# QFN-16_0_5mm.net
KiCad netlist of a schematic drawn in EAGLE
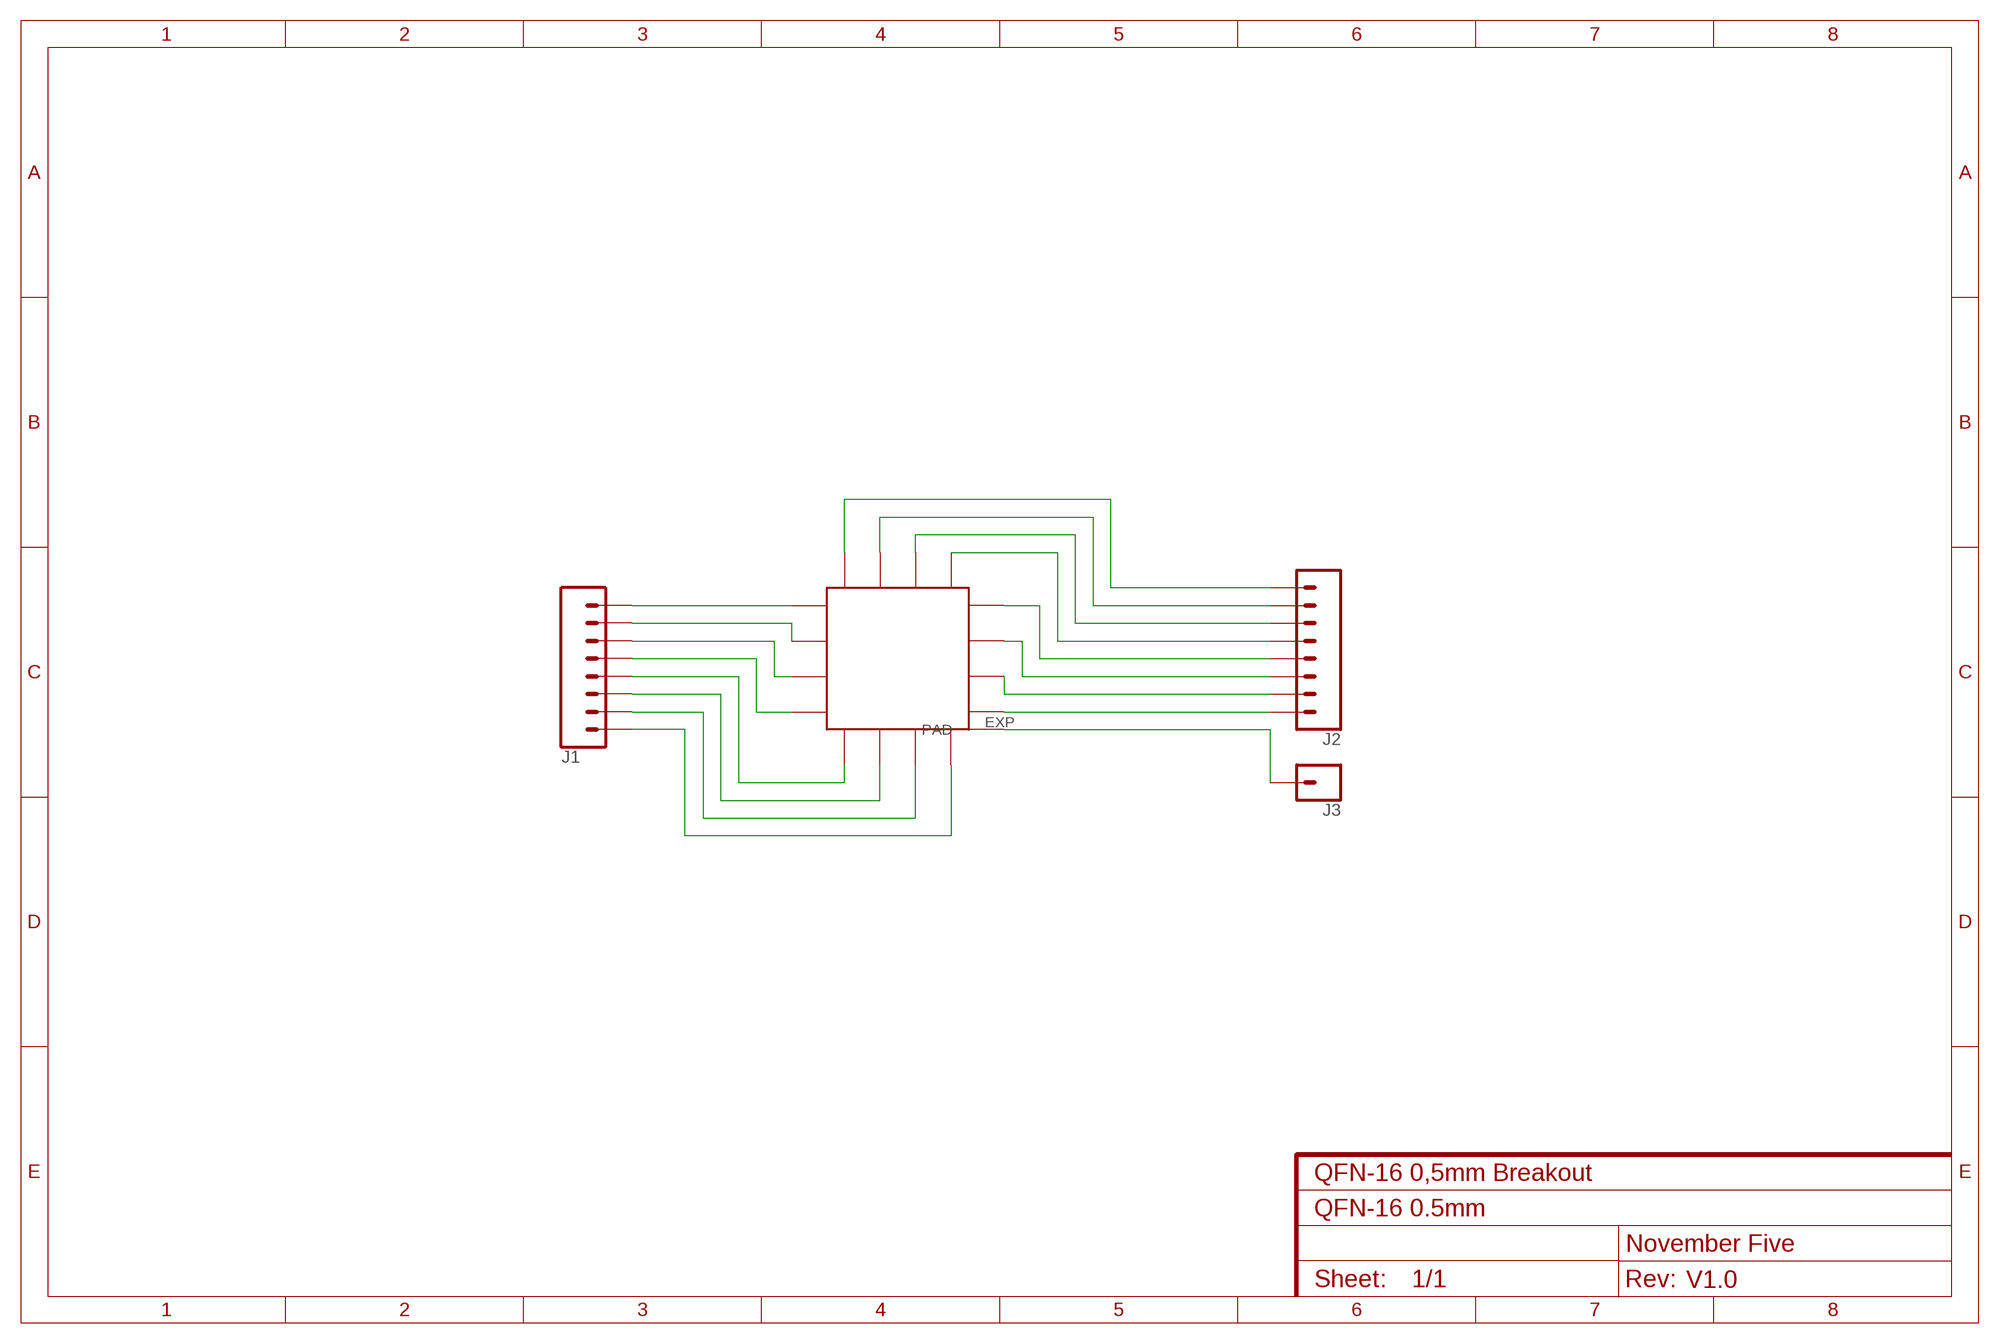
[diagram p0: schematic, sheet 1]

(export (version "E")
  (design (tool "Eeschema 10.0.6"))
  (components
    (comp (ref "J1")
      (value "CONN_08\"")
      (footprint "eagle-import:1X08")
      (libsource (lib "eagle-import") (part "CONN_08{dblquote}"))
    )
    (comp (ref "J2")
      (value "CONN_08\"")
      (footprint "eagle-import:1X08")
      (libsource (lib "eagle-import") (part "CONN_08{dblquote}"))
    )
    (comp (ref "J3")
      (value "CONN_01")
      (footprint "eagle-import:1X01")
      (libsource (lib "eagle-import") (part "CONN_01"))
    )
    (comp (ref "U$1")
      (value "QFN-16_0,5MM")
      (footprint "eagle-import:QFN16_0,5MM")
      (libsource (lib "eagle-import") (part "QFN-16_0,5MM"))
    )
  )
  (nets
    (net (code "1") (name "Net-(U$1-PAD)") (class "Default")
      (node (ref "J3") (pin "1") (pinfunction "1_1") (pintype "passive"))
      (node (ref "U$1") (pin "EXP") (pinfunction "PAD_EXP") (pintype "bidirectional"))
    )
    (net (code "2") (name "Net-(U$1-PIN1)") (class "Default")
      (node (ref "J1") (pin "1") (pinfunction "1_1") (pintype "passive"))
      (node (ref "U$1") (pin "1") (pinfunction "PIN1_1") (pintype "bidirectional"))
    )
    (net (code "3") (name "Net-(U$1-PIN2)") (class "Default")
      (node (ref "J1") (pin "2") (pinfunction "2_2") (pintype "passive"))
      (node (ref "U$1") (pin "2") (pinfunction "PIN2_2") (pintype "bidirectional"))
    )
    (net (code "4") (name "Net-(U$1-PIN3)") (class "Default")
      (node (ref "J1") (pin "3") (pinfunction "3_3") (pintype "passive"))
      (node (ref "U$1") (pin "3") (pinfunction "PIN3_3") (pintype "bidirectional"))
    )
    (net (code "5") (name "Net-(U$1-PIN4)") (class "Default")
      (node (ref "J1") (pin "4") (pinfunction "4_4") (pintype "passive"))
      (node (ref "U$1") (pin "4") (pinfunction "PIN4_4") (pintype "bidirectional"))
    )
    (net (code "6") (name "Net-(U$1-PIN5)") (class "Default")
      (node (ref "J1") (pin "5") (pinfunction "5_5") (pintype "passive"))
      (node (ref "U$1") (pin "5") (pinfunction "PIN5_5") (pintype "bidirectional"))
    )
    (net (code "7") (name "Net-(U$1-PIN6)") (class "Default")
      (node (ref "J1") (pin "6") (pinfunction "6_6") (pintype "passive"))
      (node (ref "U$1") (pin "6") (pinfunction "PIN6_6") (pintype "bidirectional"))
    )
    (net (code "8") (name "Net-(U$1-PIN7)") (class "Default")
      (node (ref "J1") (pin "7") (pinfunction "7_7") (pintype "passive"))
      (node (ref "U$1") (pin "7") (pinfunction "PIN7_7") (pintype "bidirectional"))
    )
    (net (code "9") (name "Net-(U$1-PIN8)") (class "Default")
      (node (ref "J1") (pin "8") (pinfunction "8_8") (pintype "passive"))
      (node (ref "U$1") (pin "8") (pinfunction "PIN8_8") (pintype "bidirectional"))
    )
    (net (code "10") (name "Net-(U$1-PIN9)") (class "Default")
      (node (ref "J2") (pin "8") (pinfunction "8_8") (pintype "passive"))
      (node (ref "U$1") (pin "9") (pinfunction "PIN9_9") (pintype "bidirectional"))
    )
    (net (code "11") (name "Net-(U$1-PIN10)") (class "Default")
      (node (ref "J2") (pin "7") (pinfunction "7_7") (pintype "passive"))
      (node (ref "U$1") (pin "10") (pinfunction "PIN10_10") (pintype "bidirectional"))
    )
    (net (code "12") (name "Net-(U$1-PIN11)") (class "Default")
      (node (ref "J2") (pin "6") (pinfunction "6_6") (pintype "passive"))
      (node (ref "U$1") (pin "11") (pinfunction "PIN11_11") (pintype "bidirectional"))
    )
    (net (code "13") (name "Net-(U$1-PIN12)") (class "Default")
      (node (ref "J2") (pin "5") (pinfunction "5_5") (pintype "passive"))
      (node (ref "U$1") (pin "12") (pinfunction "PIN12_12") (pintype "bidirectional"))
    )
    (net (code "14") (name "Net-(U$1-PIN13)") (class "Default")
      (node (ref "J2") (pin "4") (pinfunction "4_4") (pintype "passive"))
      (node (ref "U$1") (pin "13") (pinfunction "PIN13_13") (pintype "bidirectional"))
    )
    (net (code "15") (name "Net-(U$1-PIN14)") (class "Default")
      (node (ref "J2") (pin "3") (pinfunction "3_3") (pintype "passive"))
      (node (ref "U$1") (pin "14") (pinfunction "PIN14_14") (pintype "bidirectional"))
    )
    (net (code "16") (name "Net-(U$1-PIN15)") (class "Default")
      (node (ref "J2") (pin "2") (pinfunction "2_2") (pintype "passive"))
      (node (ref "U$1") (pin "15") (pinfunction "PIN15_15") (pintype "bidirectional"))
    )
    (net (code "17") (name "Net-(U$1-PIN16)") (class "Default")
      (node (ref "J2") (pin "1") (pinfunction "1_1") (pintype "passive"))
      (node (ref "U$1") (pin "16") (pinfunction "PIN16_16") (pintype "bidirectional"))
    )
  )
)
